# LED_Control_Board.net
KiCad netlist of a schematic drawn in Altium Designer
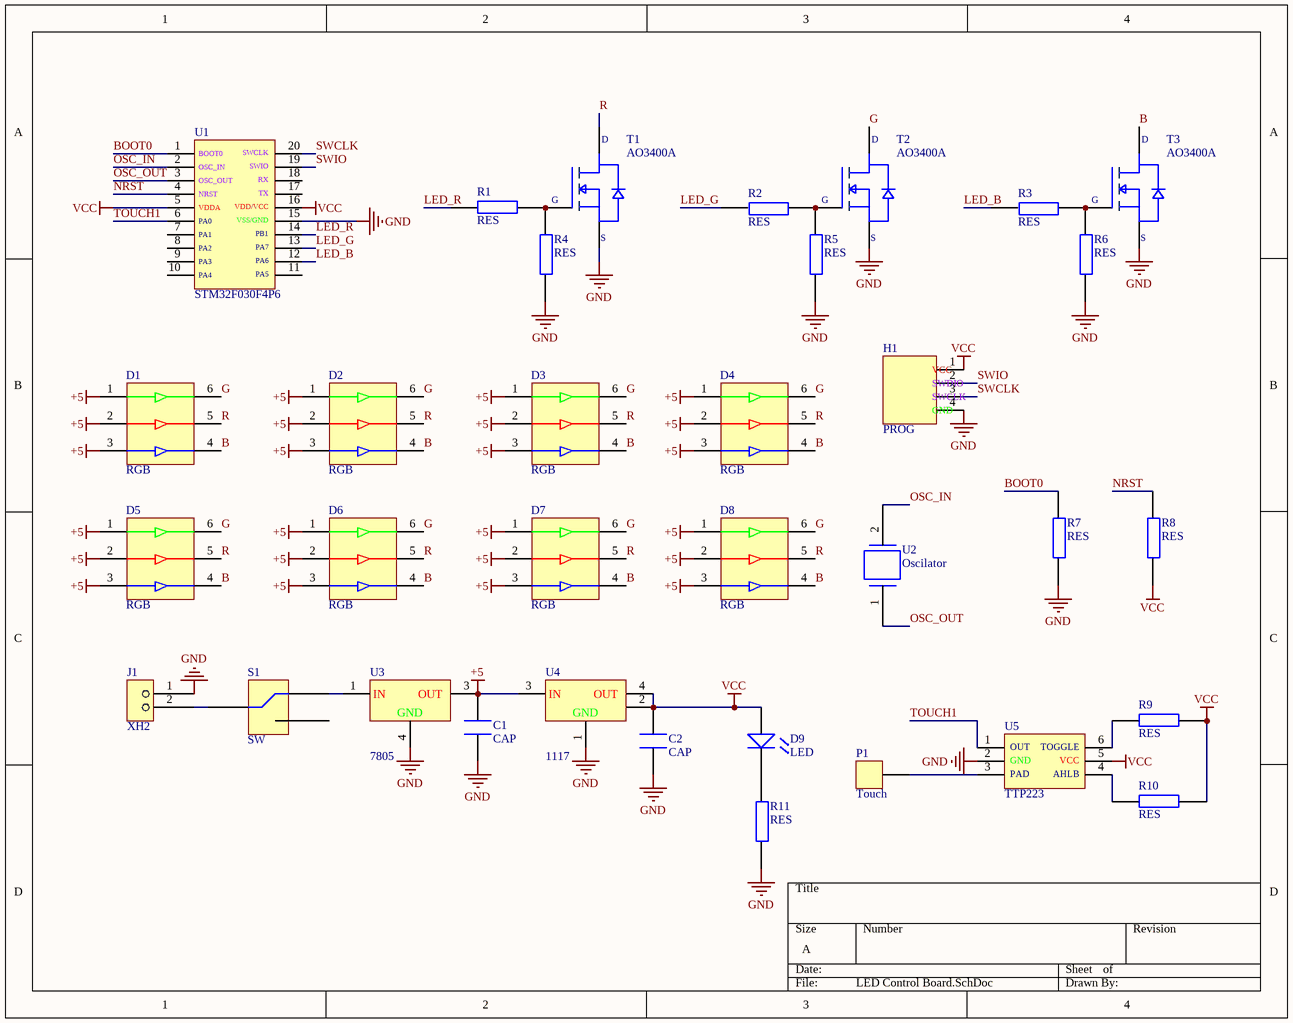
[diagram p0: LED Control Board.SchDoc]

(export (version "E")
  (design (tool "Eeschema 10.0.6"))
  (components
    (comp (ref "C1")
      (value "CAP")
      (footprint "CAP1206")
      (description "Capacitor SMD 1206")
      (libsource (lib "Farhan") (part "CAP1206"))
    )
    (comp (ref "C2")
      (value "CAP")
      (footprint "CAP1206")
      (description "Capacitor SMD 1206")
      (libsource (lib "Farhan") (part "CAP1206"))
    )
    (comp (ref "D1")
      (value "RGB")
      (footprint "RGB LED SMD")
      (description "RGB LED SMD")
      (libsource (lib "Farhan") (part "RGB LED SMD"))
    )
    (comp (ref "D2")
      (value "RGB")
      (footprint "RGB LED SMD")
      (description "RGB LED SMD")
      (libsource (lib "Farhan") (part "RGB LED SMD"))
    )
    (comp (ref "D3")
      (value "RGB")
      (footprint "RGB LED SMD")
      (description "RGB LED SMD")
      (libsource (lib "Farhan") (part "RGB LED SMD"))
    )
    (comp (ref "D4")
      (value "RGB")
      (footprint "RGB LED SMD")
      (description "RGB LED SMD")
      (libsource (lib "Farhan") (part "RGB LED SMD"))
    )
    (comp (ref "D5")
      (value "RGB")
      (footprint "RGB LED SMD")
      (description "RGB LED SMD")
      (libsource (lib "Farhan") (part "RGB LED SMD"))
    )
    (comp (ref "D6")
      (value "RGB")
      (footprint "RGB LED SMD")
      (description "RGB LED SMD")
      (libsource (lib "Farhan") (part "RGB LED SMD"))
    )
    (comp (ref "D7")
      (value "RGB")
      (footprint "RGB LED SMD")
      (description "RGB LED SMD")
      (libsource (lib "Farhan") (part "RGB LED SMD"))
    )
    (comp (ref "D8")
      (value "RGB")
      (footprint "RGB LED SMD")
      (description "RGB LED SMD")
      (libsource (lib "Farhan") (part "RGB LED SMD"))
    )
    (comp (ref "D9")
      (value "LED")
      (footprint "LED RED 1206")
      (description "LED SMD 1206")
      (libsource (lib "Farhan") (part "LED SMD 1206"))
    )
    (comp (ref "H1") (value "PROG") (footprint "PROGRAMER") (libsource (lib "Farhan") (part "Programmer")))
    (comp (ref "J1")
      (value "XH2")
      (footprint "XH 2pin")
      (description "XH Connector 2pins")
      (libsource (lib "Farhan") (part "XH 2PIN"))
    )
    (comp (ref "P1")
      (value "Touch")
      (footprint "Touch")
      (description "Touch Pad")
      (libsource (lib "Farhan") (part "Touch"))
    )
    (comp (ref "R1")
      (value "RES")
      (footprint "RES1206")
      (description "RESISTOR SMD")
      (libsource (lib "Farhan") (part "RES1206"))
    )
    (comp (ref "R2")
      (value "RES")
      (footprint "RES1206")
      (description "RESISTOR SMD")
      (libsource (lib "Farhan") (part "RES1206"))
    )
    (comp (ref "R3")
      (value "RES")
      (footprint "RES1206")
      (description "RESISTOR SMD")
      (libsource (lib "Farhan") (part "RES1206"))
    )
    (comp (ref "R4")
      (value "RES")
      (footprint "RES1206")
      (description "RESISTOR SMD")
      (libsource (lib "Farhan") (part "RES1206"))
    )
    (comp (ref "R5")
      (value "RES")
      (footprint "RES1206")
      (description "RESISTOR SMD")
      (libsource (lib "Farhan") (part "RES1206"))
    )
    (comp (ref "R6")
      (value "RES")
      (footprint "RES1206")
      (description "RESISTOR SMD")
      (libsource (lib "Farhan") (part "RES1206"))
    )
    (comp (ref "R7")
      (value "RES")
      (footprint "RES1206")
      (description "RESISTOR SMD")
      (libsource (lib "Farhan") (part "RES1206"))
    )
    (comp (ref "R8")
      (value "RES")
      (footprint "RES1206")
      (description "RESISTOR SMD")
      (libsource (lib "Farhan") (part "RES1206"))
    )
    (comp (ref "R9")
      (value "RES")
      (footprint "RES805")
      (description "RESISTOR SMD")
      (libsource (lib "Farhan") (part "RES805"))
    )
    (comp (ref "R10")
      (value "RES")
      (footprint "RES805")
      (description "RESISTOR SMD")
      (libsource (lib "Farhan") (part "RES805"))
    )
    (comp (ref "R11")
      (value "RES")
      (footprint "RES1206")
      (description "RESISTOR SMD")
      (libsource (lib "Farhan") (part "RES1206"))
    )
    (comp (ref "S1")
      (value "SW")
      (footprint "SS-12D00G3")
      (description "SWITCH SPDT")
      (libsource (lib "Farhan") (part "SS-12D00G3"))
    )
    (comp (ref "T1") (value "AO3400A") (footprint "AO3400A") (libsource (lib "Farhan") (part "AO3400A")))
    (comp (ref "T2") (value "AO3400A") (footprint "AO3400A") (libsource (lib "Farhan") (part "AO3400A")))
    (comp (ref "T3") (value "AO3400A") (footprint "AO3400A") (libsource (lib "Farhan") (part "AO3400A")))
    (comp (ref "U1")
      (value "STM32F030F4P6")
      (footprint "STM32F030F4P6")
      (libsource (lib "Farhan") (part "STM32F030F4P6"))
    )
    (comp (ref "U2")
      (value "Oscilator")
      (footprint "Crystal Oscilator")
      (description "Crystal Oscilator 8MHz")
      (libsource (lib "Farhan") (part "Crystal"))
    )
    (comp (ref "U3")
      (value "7805")
      (footprint "7805 (SOT-252)")
      (description "5v Regulator")
      (libsource (lib "Farhan") (part "7805 (SOT-252)"))
    )
    (comp (ref "U4")
      (value "1117")
      (footprint "AMS1117")
      (description "3.3v Regulator")
      (libsource (lib "Farhan") (part "AMS1117"))
    )
    (comp (ref "U5")
      (value "TTP223")
      (footprint "TTP223")
      (description "Touch Drive IC")
      (libsource (lib "Farhan") (part "TTP223"))
    )
  )
  (nets
    (net (code "1") (name "+5") (class "Default")
      (node (ref "C1") (pin "2") (pintype "passive"))
      (node (ref "D1") (pin "1") (pintype "passive"))
      (node (ref "D1") (pin "2") (pintype "passive"))
      (node (ref "D1") (pin "3") (pintype "passive"))
      (node (ref "D2") (pin "1") (pintype "passive"))
      (node (ref "D2") (pin "2") (pintype "passive"))
      (node (ref "D2") (pin "3") (pintype "passive"))
      (node (ref "D3") (pin "1") (pintype "passive"))
      (node (ref "D3") (pin "2") (pintype "passive"))
      (node (ref "D3") (pin "3") (pintype "passive"))
      (node (ref "D4") (pin "1") (pintype "passive"))
      (node (ref "D4") (pin "2") (pintype "passive"))
      (node (ref "D4") (pin "3") (pintype "passive"))
      (node (ref "D5") (pin "1") (pintype "passive"))
      (node (ref "D5") (pin "2") (pintype "passive"))
      (node (ref "D5") (pin "3") (pintype "passive"))
      (node (ref "D6") (pin "1") (pintype "passive"))
      (node (ref "D6") (pin "2") (pintype "passive"))
      (node (ref "D6") (pin "3") (pintype "passive"))
      (node (ref "D7") (pin "1") (pintype "passive"))
      (node (ref "D7") (pin "2") (pintype "passive"))
      (node (ref "D7") (pin "3") (pintype "passive"))
      (node (ref "D8") (pin "1") (pintype "passive"))
      (node (ref "D8") (pin "2") (pintype "passive"))
      (node (ref "D8") (pin "3") (pintype "passive"))
      (node (ref "U3") (pin "3") (pintype "passive"))
      (node (ref "U4") (pin "3") (pintype "passive"))
    )
    (net (code "2") (name "/B") (class "Default")
      (node (ref "D1") (pin "4") (pintype "passive"))
      (node (ref "D2") (pin "4") (pintype "passive"))
      (node (ref "D3") (pin "4") (pintype "passive"))
      (node (ref "D4") (pin "4") (pintype "passive"))
      (node (ref "D5") (pin "4") (pintype "passive"))
      (node (ref "D6") (pin "4") (pintype "passive"))
      (node (ref "D7") (pin "4") (pintype "passive"))
      (node (ref "D8") (pin "4") (pintype "passive"))
      (node (ref "T3") (pin "3") (pintype "passive"))
    )
    (net (code "3") (name "/BOOT0") (class "Default")
      (node (ref "R7") (pin "1") (pintype "passive"))
      (node (ref "U1") (pin "1") (pintype "passive"))
    )
    (net (code "4") (name "/G") (class "Default")
      (node (ref "D1") (pin "6") (pintype "passive"))
      (node (ref "D2") (pin "6") (pintype "passive"))
      (node (ref "D3") (pin "6") (pintype "passive"))
      (node (ref "D4") (pin "6") (pintype "passive"))
      (node (ref "D5") (pin "6") (pintype "passive"))
      (node (ref "D6") (pin "6") (pintype "passive"))
      (node (ref "D7") (pin "6") (pintype "passive"))
      (node (ref "D8") (pin "6") (pintype "passive"))
      (node (ref "T2") (pin "3") (pintype "passive"))
    )
    (net (code "5") (name "/LED_B") (class "Default")
      (node (ref "R3") (pin "2") (pintype "passive"))
      (node (ref "U1") (pin "12") (pintype "passive"))
    )
    (net (code "6") (name "/LED_G") (class "Default")
      (node (ref "R2") (pin "2") (pintype "passive"))
      (node (ref "U1") (pin "13") (pintype "passive"))
    )
    (net (code "7") (name "/LED_R") (class "Default")
      (node (ref "R1") (pin "1") (pintype "passive"))
      (node (ref "U1") (pin "14") (pintype "passive"))
    )
    (net (code "8") (name "/NRST") (class "Default")
      (node (ref "R8") (pin "1") (pintype "passive"))
      (node (ref "U1") (pin "4") (pintype "passive"))
    )
    (net (code "9") (name "/OSC_IN") (class "Default")
      (node (ref "U1") (pin "2") (pintype "passive"))
      (node (ref "U2") (pin "2") (pintype "passive"))
    )
    (net (code "10") (name "/OSC_OUT") (class "Default")
      (node (ref "U1") (pin "3") (pintype "passive"))
      (node (ref "U2") (pin "1") (pintype "passive"))
    )
    (net (code "11") (name "/R") (class "Default")
      (node (ref "D1") (pin "5") (pintype "passive"))
      (node (ref "D2") (pin "5") (pintype "passive"))
      (node (ref "D3") (pin "5") (pintype "passive"))
      (node (ref "D4") (pin "5") (pintype "passive"))
      (node (ref "D5") (pin "5") (pintype "passive"))
      (node (ref "D6") (pin "5") (pintype "passive"))
      (node (ref "D7") (pin "5") (pintype "passive"))
      (node (ref "D8") (pin "5") (pintype "passive"))
      (node (ref "T1") (pin "3") (pintype "passive"))
    )
    (net (code "12") (name "/SWCLK") (class "Default")
      (node (ref "H1") (pin "3") (pintype "passive"))
      (node (ref "U1") (pin "20") (pintype "passive"))
    )
    (net (code "13") (name "/SWIO") (class "Default")
      (node (ref "H1") (pin "2") (pintype "passive"))
      (node (ref "U1") (pin "19") (pintype "passive"))
    )
    (net (code "14") (name "/TOUCH1") (class "Default")
      (node (ref "U1") (pin "6") (pintype "passive"))
      (node (ref "U5") (pin "1") (pintype "passive"))
    )
    (net (code "15") (name "GND") (class "Default")
      (node (ref "C1") (pin "1") (pintype "passive"))
      (node (ref "C2") (pin "1") (pintype "passive"))
      (node (ref "H1") (pin "4") (pintype "passive"))
      (node (ref "J1") (pin "1") (pintype "passive"))
      (node (ref "R11") (pin "2") (pintype "passive"))
      (node (ref "R4") (pin "2") (pintype "passive"))
      (node (ref "R5") (pin "2") (pintype "passive"))
      (node (ref "R6") (pin "2") (pintype "passive"))
      (node (ref "R7") (pin "2") (pintype "passive"))
      (node (ref "T1") (pin "2") (pintype "passive"))
      (node (ref "T2") (pin "2") (pintype "passive"))
      (node (ref "T3") (pin "2") (pintype "passive"))
      (node (ref "U1") (pin "15") (pintype "passive"))
      (node (ref "U3") (pin "4") (pintype "passive"))
      (node (ref "U4") (pin "1") (pintype "passive"))
      (node (ref "U5") (pin "2") (pintype "passive"))
    )
    (net (code "16") (name "Net-(D9-Pad2)") (class "Default")
      (node (ref "D9") (pin "2") (pintype "passive"))
      (node (ref "R11") (pin "1") (pintype "passive"))
    )
    (net (code "17") (name "Net-(J1-Pad2)") (class "Default")
      (node (ref "J1") (pin "2") (pintype "passive"))
      (node (ref "S1") (pin "2") (pintype "passive"))
    )
    (net (code "18") (name "Net-(P1-Pad1)") (class "Default")
      (node (ref "P1") (pin "1") (pintype "passive"))
      (node (ref "U5") (pin "3") (pintype "passive"))
    )
    (net (code "19") (name "Net-(R1-Pad2)") (class "Default")
      (node (ref "R1") (pin "2") (pintype "passive"))
      (node (ref "R4") (pin "1") (pintype "passive"))
      (node (ref "T1") (pin "1") (pintype "passive"))
    )
    (net (code "20") (name "Net-(R2-Pad1)") (class "Default")
      (node (ref "R2") (pin "1") (pintype "passive"))
      (node (ref "R5") (pin "1") (pintype "passive"))
      (node (ref "T2") (pin "1") (pintype "passive"))
    )
    (net (code "21") (name "Net-(R3-Pad1)") (class "Default")
      (node (ref "R3") (pin "1") (pintype "passive"))
      (node (ref "R6") (pin "1") (pintype "passive"))
      (node (ref "T3") (pin "1") (pintype "passive"))
    )
    (net (code "22") (name "Net-(R9-Pad1)") (class "Default")
      (node (ref "R9") (pin "1") (pintype "passive"))
      (node (ref "U5") (pin "6") (pintype "passive"))
    )
    (net (code "23") (name "Net-(R10-Pad1)") (class "Default")
      (node (ref "R10") (pin "1") (pintype "passive"))
      (node (ref "U5") (pin "4") (pintype "passive"))
    )
    (net (code "24") (name "Net-(S1-Pad1)") (class "Default")
      (node (ref "S1") (pin "1") (pintype "passive"))
      (node (ref "U3") (pin "1") (pintype "passive"))
    )
    (net (code "25") (name "VCC") (class "Default")
      (node (ref "C2") (pin "2") (pintype "passive"))
      (node (ref "D9") (pin "1") (pintype "passive"))
      (node (ref "H1") (pin "1") (pintype "passive"))
      (node (ref "R10") (pin "2") (pintype "passive"))
      (node (ref "R8") (pin "2") (pintype "passive"))
      (node (ref "R9") (pin "2") (pintype "passive"))
      (node (ref "U1") (pin "16") (pintype "passive"))
      (node (ref "U1") (pin "5") (pintype "passive"))
      (node (ref "U4") (pin "2") (pintype "passive"))
      (node (ref "U4") (pin "4") (pintype "passive"))
      (node (ref "U5") (pin "5") (pintype "passive"))
    )
    (net (code "26") (name "unconnected-(S1-Pad3)") (class "Default")
      (node (ref "S1") (pin "3") (pintype "passive"))
    )
    (net (code "27") (name "unconnected-(U1-Pad7)") (class "Default")
      (node (ref "U1") (pin "7") (pintype "passive"))
    )
    (net (code "28") (name "unconnected-(U1-Pad8)") (class "Default")
      (node (ref "U1") (pin "8") (pintype "passive"))
    )
    (net (code "29") (name "unconnected-(U1-Pad9)") (class "Default")
      (node (ref "U1") (pin "9") (pintype "passive"))
    )
    (net (code "30") (name "unconnected-(U1-Pad10)") (class "Default")
      (node (ref "U1") (pin "10") (pintype "passive"))
    )
    (net (code "31") (name "unconnected-(U1-Pad11)") (class "Default")
      (node (ref "U1") (pin "11") (pintype "passive"))
    )
    (net (code "32") (name "unconnected-(U1-Pad17)") (class "Default")
      (node (ref "U1") (pin "17") (pintype "passive"))
    )
    (net (code "33") (name "unconnected-(U1-Pad18)") (class "Default")
      (node (ref "U1") (pin "18") (pintype "passive"))
    )
  )
)
